# instrumentation-amplifier.net
KiCad netlist of a schematic drawn in EAGLE
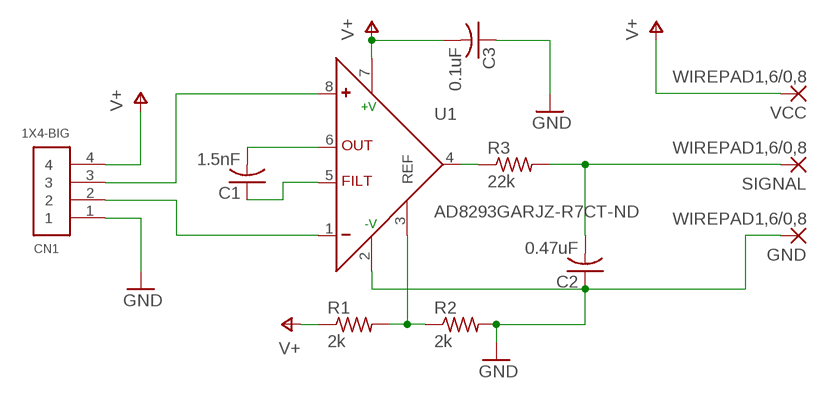
[diagram p0: schematic, sheet 1]

(export (version "E")
  (design (tool "Eeschema 10.0.6"))
  (components
    (comp (ref "C1")
      (value "1.5nF")
      (footprint "eagle-import:C025-024X044")
      (libsource (lib "eagle-import") (part "C-US025-024X044"))
    )
    (comp (ref "C2")
      (value "0.47uF")
      (footprint "eagle-import:C050-024X044")
      (libsource (lib "eagle-import") (part "C-US050-024X044"))
    )
    (comp (ref "C3")
      (value "0.1uF")
      (footprint "eagle-import:C050-024X044")
      (libsource (lib "eagle-import") (part "C-US050-024X044"))
    )
    (comp (ref "CN1")
      (value "1X4-BIG")
      (footprint "eagle-import:1X04-BIG")
      (libsource (lib "eagle-import") (part "1X4-BIG"))
    )
    (comp (ref "GND")
      (value "WIREPAD1,6/0,8")
      (footprint "eagle-import:1,6_0,8")
      (libsource (lib "eagle-import") (part "WIREPAD1,6/0,8"))
    )
    (comp (ref "R1")
      (value "2k")
      (footprint "eagle-import:R0603")
      (libsource (lib "eagle-import") (part "R-US_R0603"))
    )
    (comp (ref "R2")
      (value "2k")
      (footprint "eagle-import:R0603")
      (libsource (lib "eagle-import") (part "R-US_R0603"))
    )
    (comp (ref "R3")
      (value "22k")
      (footprint "eagle-import:R0603")
      (libsource (lib "eagle-import") (part "R-US_R0603"))
    )
    (comp (ref "SIGNAL")
      (value "WIREPAD1,6/0,8")
      (footprint "eagle-import:1,6_0,8")
      (libsource (lib "eagle-import") (part "WIREPAD1,6/0,8"))
    )
    (comp (ref "U1")
      (value "AD8293GARJZ-R7CT-ND")
      (footprint "eagle-import:SOT23-8")
      (libsource (lib "eagle-import") (part "AD8293GARJZ-R7CT-ND"))
    )
    (comp (ref "VCC")
      (value "WIREPAD1,6/0,8")
      (footprint "eagle-import:1,6_0,8")
      (libsource (lib "eagle-import") (part "WIREPAD1,6/0,8"))
    )
  )
  (nets
    (net (code "1") (name "GND") (class "Default")
      (node (ref "C2") (pin "1") (pinfunction "1_1") (pintype "passive"))
      (node (ref "C3") (pin "1") (pinfunction "1_1") (pintype "passive"))
      (node (ref "CN1") (pin "1") (pinfunction "1_1") (pintype "bidirectional"))
      (node (ref "GND") (pin "1") (pinfunction "P_1") (pintype "passive"))
      (node (ref "R2") (pin "2") (pinfunction "2_2") (pintype "passive"))
      (node (ref "U1") (pin "2") (pinfunction "-V_2") (pintype "power_in"))
    )
    (net (code "2") (name "Net-(SIGNAL-P)") (class "Default")
      (node (ref "C2") (pin "2") (pinfunction "2_2") (pintype "passive"))
      (node (ref "R3") (pin "2") (pinfunction "2_2") (pintype "passive"))
      (node (ref "SIGNAL") (pin "1") (pinfunction "P_1") (pintype "passive"))
    )
    (net (code "3") (name "Net-(U1-+)") (class "Default")
      (node (ref "CN1") (pin "3") (pinfunction "3_3") (pintype "bidirectional"))
      (node (ref "U1") (pin "8") (pinfunction "+_8") (pintype "input"))
    )
    (net (code "4") (name "Net-(U1--)") (class "Default")
      (node (ref "CN1") (pin "2") (pinfunction "2_2") (pintype "bidirectional"))
      (node (ref "U1") (pin "1") (pinfunction "-_1") (pintype "input"))
    )
    (net (code "5") (name "Net-(U1-ADC-OUT)") (class "Default")
      (node (ref "R3") (pin "1") (pinfunction "1_1") (pintype "passive"))
      (node (ref "U1") (pin "4") (pinfunction "ADC-OUT_4") (pintype "output"))
    )
    (net (code "6") (name "Net-(U1-FILT)") (class "Default")
      (node (ref "C1") (pin "1") (pinfunction "1_1") (pintype "passive"))
      (node (ref "U1") (pin "5") (pinfunction "FILT_5") (pintype "passive"))
    )
    (net (code "7") (name "Net-(U1-OUT)") (class "Default")
      (node (ref "C1") (pin "2") (pinfunction "2_2") (pintype "passive"))
      (node (ref "U1") (pin "6") (pinfunction "OUT_6") (pintype "passive"))
    )
    (net (code "8") (name "Net-(U1-REF)") (class "Default")
      (node (ref "R1") (pin "2") (pinfunction "2_2") (pintype "passive"))
      (node (ref "R2") (pin "1") (pinfunction "1_1") (pintype "passive"))
      (node (ref "U1") (pin "3") (pinfunction "REF_3") (pintype "passive"))
    )
    (net (code "9") (name "V+") (class "Default")
      (node (ref "C3") (pin "2") (pinfunction "2_2") (pintype "passive"))
      (node (ref "CN1") (pin "4") (pinfunction "4_4") (pintype "bidirectional"))
      (node (ref "R1") (pin "1") (pinfunction "1_1") (pintype "passive"))
      (node (ref "U1") (pin "7") (pinfunction "+V_7") (pintype "power_in"))
      (node (ref "VCC") (pin "1") (pinfunction "P_1") (pintype "passive"))
    )
  )
)
